# LightSchematic.net
KiCad netlist of a schematic drawn in EAGLE
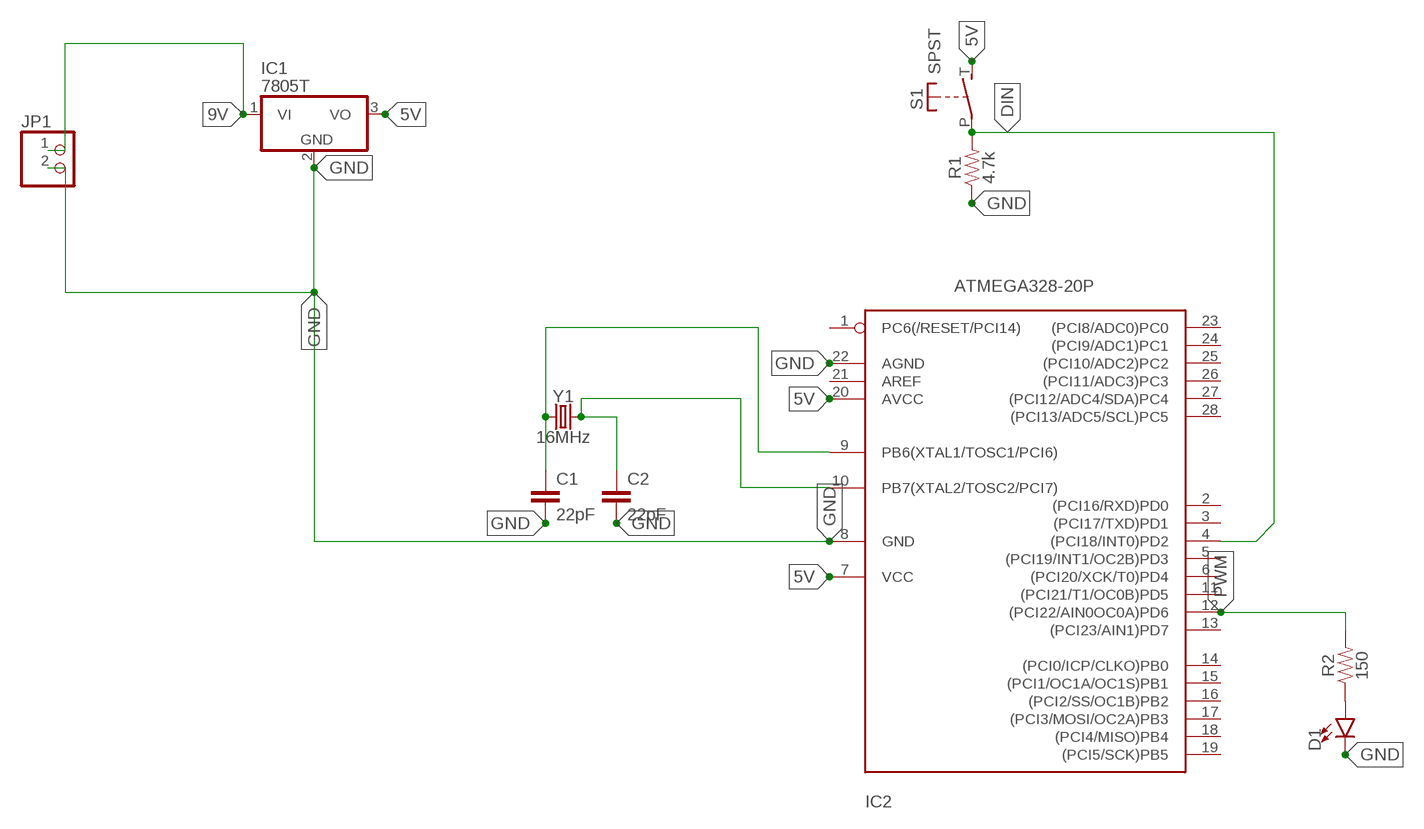
[diagram p0: schematic, sheet 1]

(export (version "E")
  (design (tool "Eeschema 10.0.6"))
  (components
    (comp (ref "C1")
      (value "22pF")
      (footprint "eagle-import:0603")
      (libsource (lib "eagle-import") (part "22PF-0603-50V-5%"))
    )
    (comp (ref "C2")
      (value "22pF")
      (footprint "eagle-import:0603")
      (libsource (lib "eagle-import") (part "22PF-0603-50V-5%"))
    )
    (comp (ref "D1")
      (value "LED1206")
      (footprint "eagle-import:LED-1206")
      (libsource (lib "eagle-import") (part "LED1206"))
    )
    (comp (ref "IC1")
      (value "7805T")
      (footprint "eagle-import:TO220H")
      (libsource (lib "eagle-import") (part "78T05"))
    )
    (comp (ref "IC2")
      (value "ATMEGA328-20P")
      (footprint "eagle-import:DIL28-3")
      (libsource (lib "eagle-import") (part "ATMEGA328P-20"))
    )
    (comp (ref "JP1")
      (value "PINHD-1X2")
      (footprint "eagle-import:1X02")
      (libsource (lib "eagle-import") (part "PINHD-1X2"))
    )
    (comp (ref "R1")
      (value "4.7k")
      (footprint "eagle-import:0402")
      (libsource (lib "eagle-import") (part "100KOHM-0402-1/16W-1%"))
    )
    (comp (ref "R2")
      (value "150")
      (footprint "eagle-import:0402")
      (libsource (lib "eagle-import") (part "100KOHM-0402-1/16W-1%"))
    )
    (comp (ref "S1")
      (value "SPST")
      (footprint "eagle-import:JUDCOSPST")
      (libsource (lib "eagle-import") (part "SPST"))
    )
    (comp (ref "Y1")
      (value "16MHz")
      (footprint "eagle-import:HC49US")
      (libsource (lib "eagle-import") (part "CRYSTAL-16MHZPTH-HC49US"))
    )
  )
  (nets
    (net (code "1") (name "5V") (class "Default")
      (node (ref "IC1") (pin "3") (pinfunction "VO_3") (pintype "passive"))
      (node (ref "IC2") (pin "20") (pinfunction "AVCC_20") (pintype "bidirectional"))
      (node (ref "IC2") (pin "7") (pinfunction "VCC_7") (pintype "bidirectional"))
      (node (ref "S1") (pin "T") (pinfunction "S_T") (pintype "passive"))
    )
    (net (code "2") (name "9V") (class "Default")
      (node (ref "IC1") (pin "1") (pinfunction "VI_1") (pintype "input"))
      (node (ref "JP1") (pin "1") (pinfunction "1_1") (pintype "passive"))
    )
    (net (code "3") (name "DIN") (class "Default")
      (node (ref "IC2") (pin "4") (pinfunction "(PCI18/INT0)PD2_4") (pintype "bidirectional"))
      (node (ref "R1") (pin "2") (pinfunction "2_2") (pintype "passive"))
      (node (ref "S1") (pin "P") (pinfunction "P_P") (pintype "passive"))
    )
    (net (code "4") (name "GND") (class "Default")
      (node (ref "C1") (pin "2") (pinfunction "2_2") (pintype "passive"))
      (node (ref "C2") (pin "2") (pinfunction "2_2") (pintype "passive"))
      (node (ref "D1") (pin "C") (pinfunction "C_C") (pintype "passive"))
      (node (ref "IC1") (pin "2") (pinfunction "GND_2") (pintype "passive"))
      (node (ref "IC2") (pin "22") (pinfunction "AGND_22") (pintype "bidirectional"))
      (node (ref "IC2") (pin "8") (pinfunction "GND_8") (pintype "bidirectional"))
      (node (ref "JP1") (pin "2") (pinfunction "2_2") (pintype "passive"))
      (node (ref "R1") (pin "1") (pinfunction "1_1") (pintype "passive"))
    )
    (net (code "5") (name "Net-(D1-PadA)") (class "Default")
      (node (ref "D1") (pin "A") (pinfunction "A_A") (pintype "passive"))
      (node (ref "R2") (pin "1") (pinfunction "1_1") (pintype "passive"))
    )
    (net (code "6") (name "Net-(IC2-PB6(XTAL1{slash}TOSC1{slash}PCI6))") (class "Default")
      (node (ref "C1") (pin "1") (pinfunction "1_1") (pintype "passive"))
      (node (ref "IC2") (pin "9") (pinfunction "PB6(XTAL1/TOSC1/PCI6)_9") (pintype "bidirectional"))
      (node (ref "Y1") (pin "1") (pinfunction "1_1") (pintype "passive"))
    )
    (net (code "7") (name "Net-(IC2-PB7(XTAL2{slash}TOSC2{slash}PCI7))") (class "Default")
      (node (ref "C2") (pin "1") (pinfunction "1_1") (pintype "passive"))
      (node (ref "IC2") (pin "10") (pinfunction "PB7(XTAL2/TOSC2/PCI7)_10") (pintype "bidirectional"))
      (node (ref "Y1") (pin "2") (pinfunction "2_2") (pintype "passive"))
    )
    (net (code "8") (name "PWM") (class "Default")
      (node (ref "IC2") (pin "12") (pinfunction "(PCI22/AIN0OC0A)PD6_12") (pintype "bidirectional"))
      (node (ref "R2") (pin "2") (pinfunction "2_2") (pintype "passive"))
    )
    (net (code "9") (name "unconnected-(IC2-(PCI0{slash}ICP{slash}CLKO)PB0-Pad14)") (class "Default")
      (node (ref "IC2") (pin "14") (pinfunction "(PCI0/ICP/CLKO)PB0_14") (pintype "bidirectional"))
    )
    (net (code "10") (name "unconnected-(IC2-(PCI1{slash}OC1A{slash}OC1S)PB1-Pad15)") (class "Default")
      (node (ref "IC2") (pin "15") (pinfunction "(PCI1/OC1A/OC1S)PB1_15") (pintype "bidirectional"))
    )
    (net (code "11") (name "unconnected-(IC2-(PCI2{slash}SS{slash}OC1B)PB2-Pad16)") (class "Default")
      (node (ref "IC2") (pin "16") (pinfunction "(PCI2/SS/OC1B)PB2_16") (pintype "bidirectional"))
    )
    (net (code "12") (name "unconnected-(IC2-(PCI3{slash}MOSI{slash}OC2A)PB3-Pad17)") (class "Default")
      (node (ref "IC2") (pin "17") (pinfunction "(PCI3/MOSI/OC2A)PB3_17") (pintype "bidirectional"))
    )
    (net (code "13") (name "unconnected-(IC2-(PCI4{slash}MISO)PB4-Pad18)") (class "Default")
      (node (ref "IC2") (pin "18") (pinfunction "(PCI4/MISO)PB4_18") (pintype "bidirectional"))
    )
    (net (code "14") (name "unconnected-(IC2-(PCI5{slash}SCK)PB5-Pad19)") (class "Default")
      (node (ref "IC2") (pin "19") (pinfunction "(PCI5/SCK)PB5_19") (pintype "bidirectional"))
    )
    (net (code "15") (name "unconnected-(IC2-(PCI8{slash}ADC0)PC0-Pad23)") (class "Default")
      (node (ref "IC2") (pin "23") (pinfunction "(PCI8/ADC0)PC0_23") (pintype "bidirectional"))
    )
    (net (code "16") (name "unconnected-(IC2-(PCI9{slash}ADC1)PC1-Pad24)") (class "Default")
      (node (ref "IC2") (pin "24") (pinfunction "(PCI9/ADC1)PC1_24") (pintype "bidirectional"))
    )
    (net (code "17") (name "unconnected-(IC2-(PCI10{slash}ADC2)PC2-Pad25)") (class "Default")
      (node (ref "IC2") (pin "25") (pinfunction "(PCI10/ADC2)PC2_25") (pintype "bidirectional"))
    )
    (net (code "18") (name "unconnected-(IC2-(PCI11{slash}ADC3)PC3-Pad26)") (class "Default")
      (node (ref "IC2") (pin "26") (pinfunction "(PCI11/ADC3)PC3_26") (pintype "bidirectional"))
    )
    (net (code "19") (name "unconnected-(IC2-(PCI12{slash}ADC4{slash}SDA)PC4-Pad27)") (class "Default")
      (node (ref "IC2") (pin "27") (pinfunction "(PCI12/ADC4/SDA)PC4_27") (pintype "bidirectional"))
    )
    (net (code "20") (name "unconnected-(IC2-(PCI13{slash}ADC5{slash}SCL)PC5-Pad28)") (class "Default")
      (node (ref "IC2") (pin "28") (pinfunction "(PCI13/ADC5/SCL)PC5_28") (pintype "bidirectional"))
    )
    (net (code "21") (name "unconnected-(IC2-(PCI16{slash}RXD)PD0-Pad2)") (class "Default")
      (node (ref "IC2") (pin "2") (pinfunction "(PCI16/RXD)PD0_2") (pintype "bidirectional"))
    )
    (net (code "22") (name "unconnected-(IC2-(PCI17{slash}TXD)PD1-Pad3)") (class "Default")
      (node (ref "IC2") (pin "3") (pinfunction "(PCI17/TXD)PD1_3") (pintype "bidirectional"))
    )
    (net (code "23") (name "unconnected-(IC2-(PCI19{slash}INT1{slash}OC2B)PD3-Pad5)") (class "Default")
      (node (ref "IC2") (pin "5") (pinfunction "(PCI19/INT1/OC2B)PD3_5") (pintype "bidirectional"))
    )
    (net (code "24") (name "unconnected-(IC2-(PCI20{slash}XCK{slash}T0)PD4-Pad6)") (class "Default")
      (node (ref "IC2") (pin "6") (pinfunction "(PCI20/XCK/T0)PD4_6") (pintype "bidirectional"))
    )
    (net (code "25") (name "unconnected-(IC2-(PCI21{slash}T1{slash}OC0B)PD5-Pad11)") (class "Default")
      (node (ref "IC2") (pin "11") (pinfunction "(PCI21/T1/OC0B)PD5_11") (pintype "bidirectional"))
    )
    (net (code "26") (name "unconnected-(IC2-(PCI23{slash}AIN1)PD7-Pad13)") (class "Default")
      (node (ref "IC2") (pin "13") (pinfunction "(PCI23/AIN1)PD7_13") (pintype "bidirectional"))
    )
    (net (code "27") (name "unconnected-(IC2-AREF-Pad21)") (class "Default")
      (node (ref "IC2") (pin "21") (pinfunction "AREF_21") (pintype "bidirectional"))
    )
    (net (code "28") (name "unconnected-(IC2-PC6({slash}RESET{slash}PCI14)-Pad1)") (class "Default")
      (node (ref "IC2") (pin "1") (pinfunction "PC6(/RESET/PCI14)_1") (pintype "bidirectional"))
    )
  )
)
